# EasyEDA_Source.net
KiCad netlist of a schematic drawn in EasyEDA
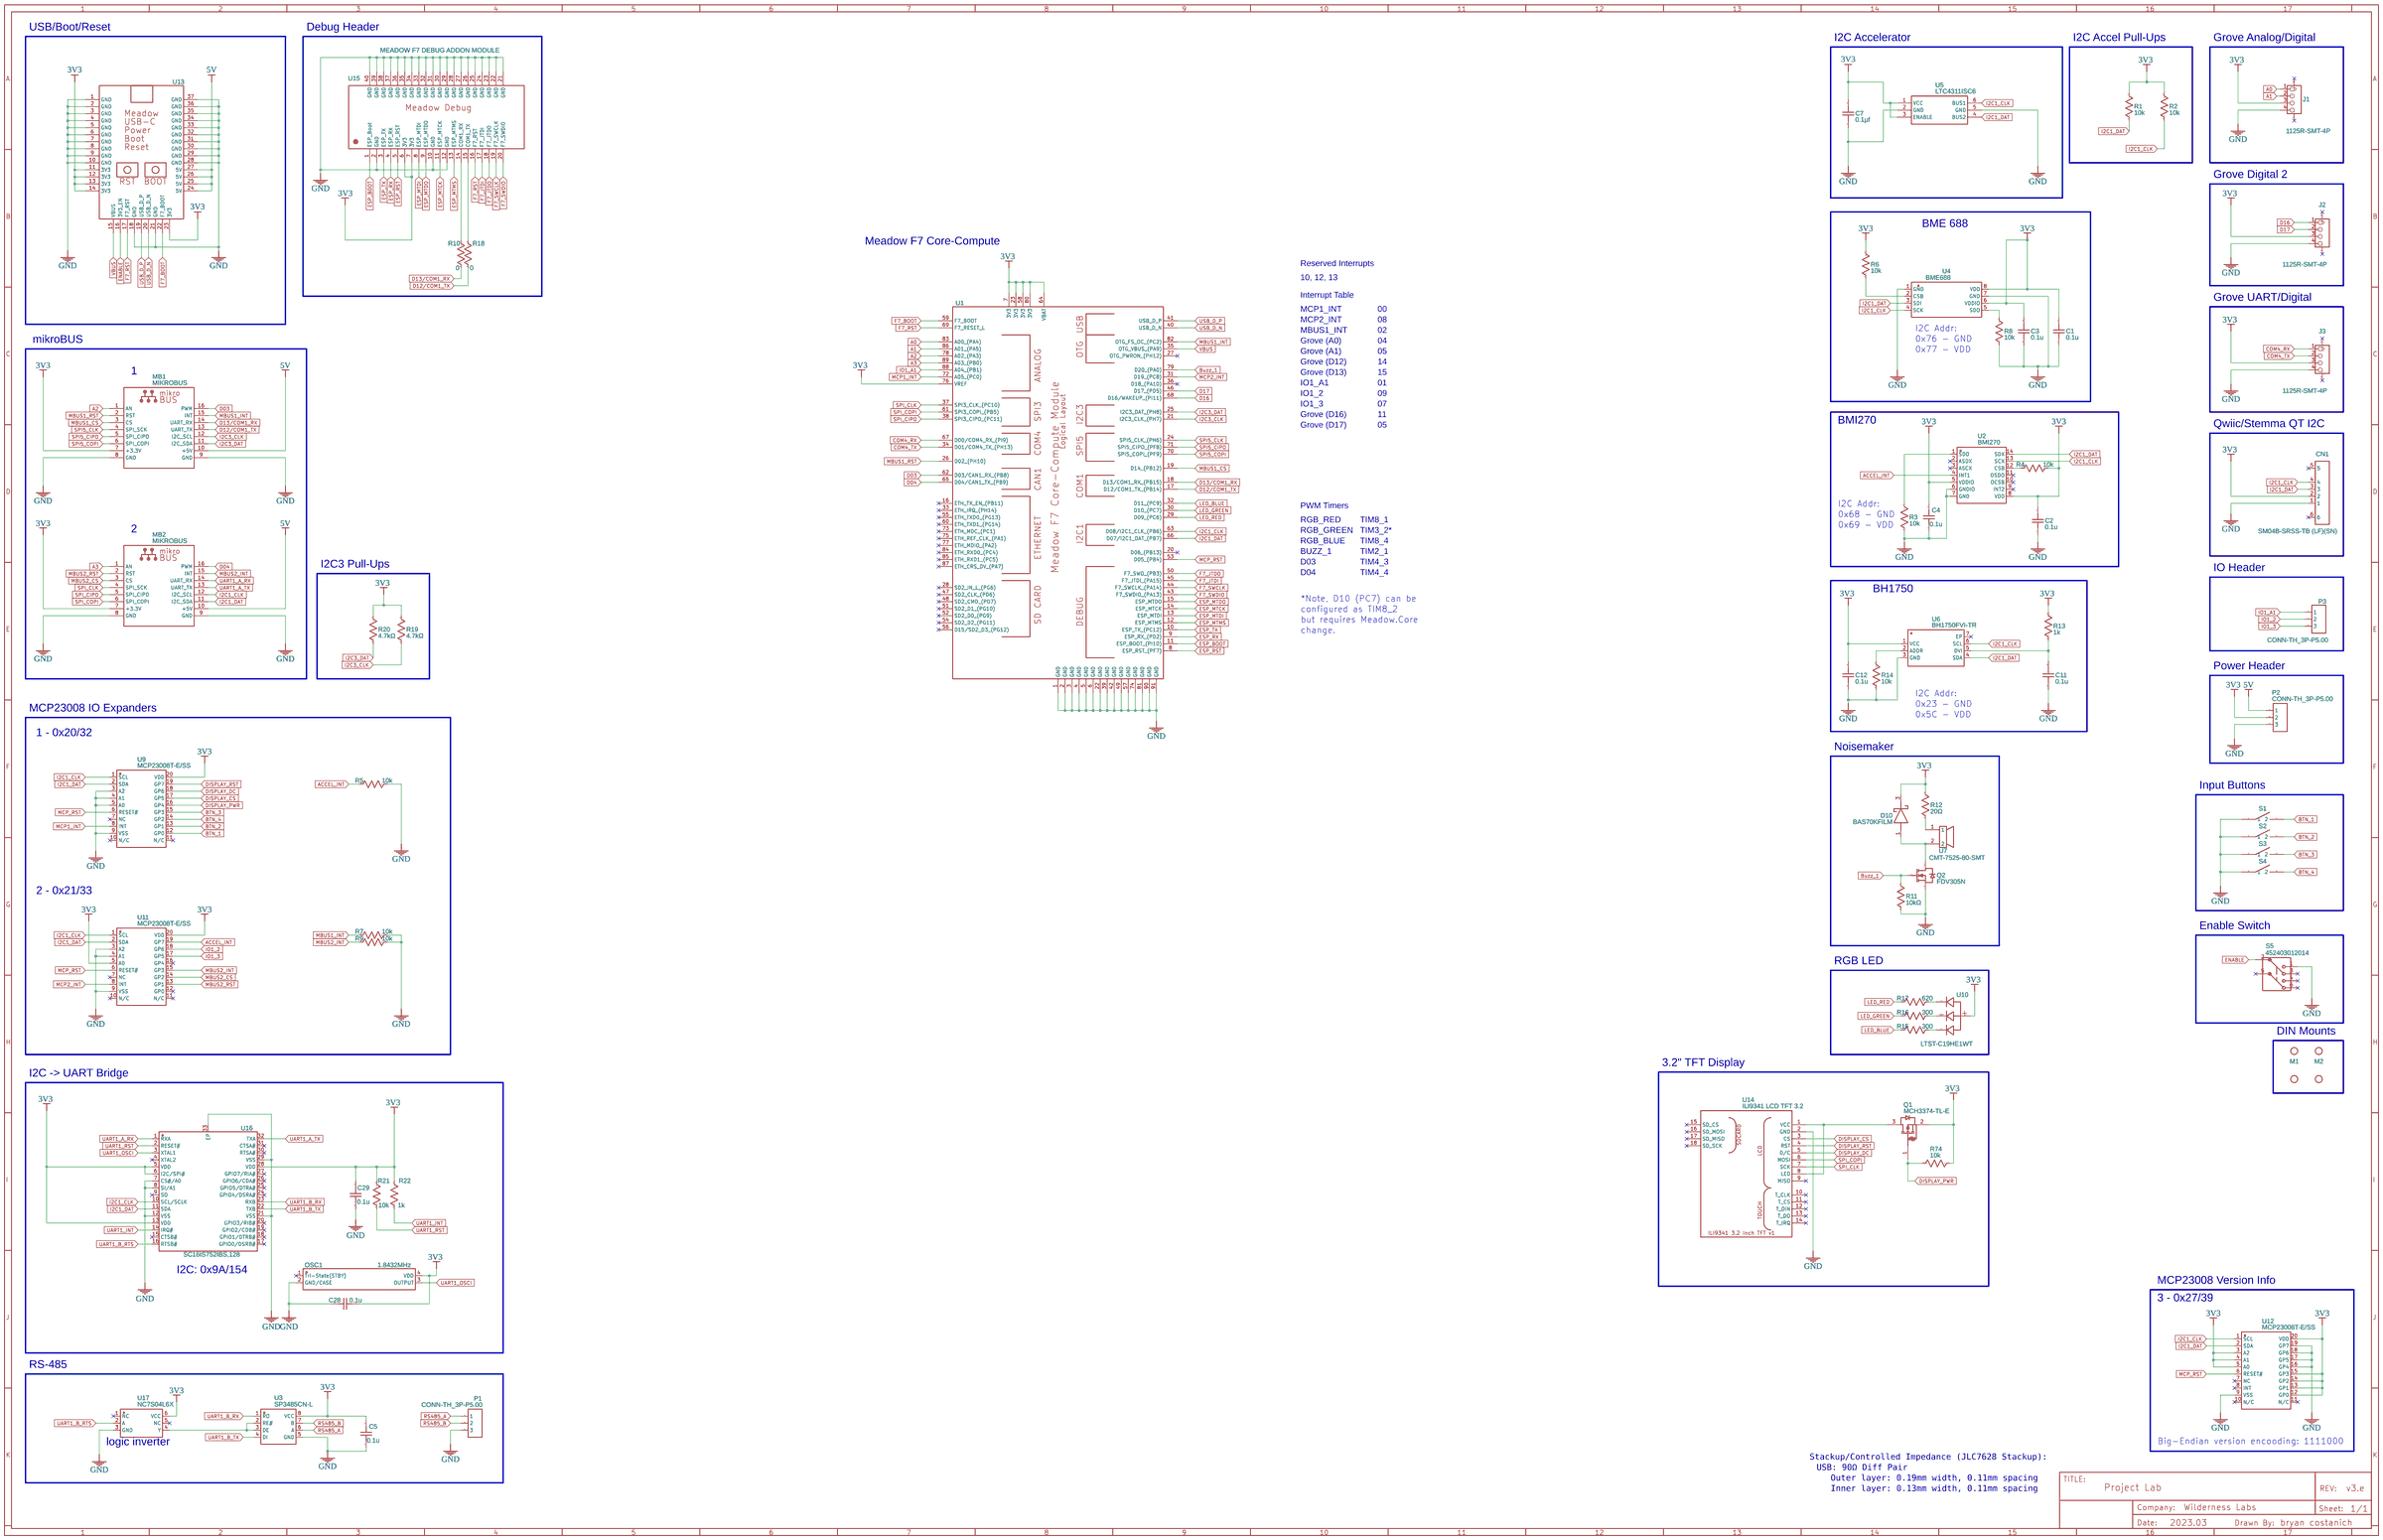
[diagram p0: schematic sheet]

(export (version "E")
  (design (tool "Eeschema 10.0.6"))
  (components
    (comp (ref "C1")
      (value "0.1u")
      (fields (field (name "BOM_Manufacturer Part") "CC0603KRX7R9BB103"))
      (libsource (lib "") (part "C_0402_US"))
    )
    (comp (ref "C2")
      (value "0.1u")
      (fields (field (name "BOM_Manufacturer Part") "CC0603KRX7R9BB103"))
      (libsource (lib "") (part "C_0402_US"))
    )
    (comp (ref "C3")
      (value "0.1u")
      (fields (field (name "BOM_Manufacturer Part") "CC0603KRX7R9BB103"))
      (libsource (lib "") (part "C_0402_US"))
    )
    (comp (ref "C4")
      (value "0.1u")
      (fields (field (name "BOM_Manufacturer Part") "CC0603KRX7R9BB103"))
      (libsource (lib "") (part "C_0402_US"))
    )
    (comp (ref "C5")
      (value "0.1u")
      (fields (field (name "BOM_Manufacturer Part") "CC0603KRX7R9BB103"))
      (libsource (lib "") (part "C_0402_US"))
    )
    (comp (ref "C7")
      (value "0.1µf")
      (fields
        (field (name "BOM_Manufacturer Part") "CC0603KRX7R7BB104")
        (field (name "BOM_Supplier Part") "C108079")
      )
      (libsource (lib "") (part "CC0603KRX7R7BB104"))
    )
    (comp (ref "C11")
      (value "0.1u")
      (fields (field (name "BOM_Manufacturer Part") "CC0603KRX7R9BB103"))
      (libsource (lib "") (part "C_0402_US"))
    )
    (comp (ref "C12")
      (value "0.1u")
      (fields (field (name "BOM_Manufacturer Part") "CC0603KRX7R9BB103"))
      (libsource (lib "") (part "C_0402_US"))
    )
    (comp (ref "C28")
      (value "0.1u")
      (fields (field (name "BOM_Manufacturer Part") "CC0603KRX7R7BB104"))
      (libsource (lib "") (part "C_0603_US_1"))
    )
    (comp (ref "C29")
      (value "0.1u")
      (fields (field (name "BOM_Manufacturer Part") "CC0603KRX7R7BB104"))
      (libsource (lib "") (part "C_0603_US"))
    )
    (comp (ref "CN1")
      (value "SM04B-SRSS-TB (LF)(SN)")
      (fields (field (name "BOM_Supplier Part") "C160404"))
      (libsource (lib "") (part "SM04B-SRSS-TB (LF)(SN)"))
    )
    (comp (ref "D10") (value "BAS70KFILM") (libsource (lib "") (part "BAS70KFILM")))
    (comp (ref "J1") (value "1125R-SMT-4P") (libsource (lib "") (part "1125R-SMT-4P")))
    (comp (ref "J2") (value "1125R-SMT-4P") (libsource (lib "") (part "1125R-SMT-4P")))
    (comp (ref "J3") (value "1125R-SMT-4P") (libsource (lib "") (part "1125R-SMT-4P")))
    (comp (ref "M1") (value "DIN_MOUNT_HOLES") (libsource (lib "") (part "DIN_MOUNT_HOLES")))
    (comp (ref "M2") (value "DIN_MOUNT_HOLES") (libsource (lib "") (part "DIN_MOUNT_HOLES")))
    (comp (ref "MB1") (value "MIKROBUS") (libsource (lib "") (part "MIKROBUS")))
    (comp (ref "MB2") (value "MIKROBUS") (libsource (lib "") (part "MIKROBUS")))
    (comp (ref "OSC1")
      (value "1.8432MHz")
      (fields (field (name "BOM_Manufacturer Part") "ASE-1.8432MHZ-LC-T"))
      (libsource (lib "") (part "ASE-1.8432MHZ-C-T3"))
    )
    (comp (ref "P1")
      (value "CONN-TH_3P-P5.00")
      (fields
        (field (name "BOM_Manufacturer Part") "39890-0303")
        (field (name "BOM_Supplier Part") "WM15826-ND")
      )
      (libsource (lib "") (part "CONN-TH_3P-P5.00"))
    )
    (comp (ref "P2")
      (value "CONN-TH_3P-P5.00")
      (fields
        (field (name "BOM_Manufacturer Part") "39890-0303")
        (field (name "BOM_Supplier Part") "WM15826-ND")
      )
      (libsource (lib "") (part "CONN-TH_3P-P5.00"))
    )
    (comp (ref "P3")
      (value "CONN-TH_3P-P5.00")
      (fields
        (field (name "BOM_Manufacturer Part") "39890-0303")
        (field (name "BOM_Supplier Part") "WM15826-ND")
      )
      (libsource (lib "") (part "CONN-TH_3P-P5.00"))
    )
    (comp (ref "Q1") (value "MCH3374-TL-E") (libsource (lib "") (part "MCH3374-TL-E")))
    (comp (ref "Q2")
      (value "FDV305N")
      (fields (field (name "BOM_Supplier Part") "C65189"))
      (libsource (lib "") (part "2N7002"))
    )
    (comp (ref "R1")
      (value "10k")
      (fields (field (name "BOM_Manufacturer Part") "RC0603FR-0710KL"))
      (libsource (lib "") (part "Res_0603(1/10W)_US"))
    )
    (comp (ref "R2")
      (value "10k")
      (fields (field (name "BOM_Manufacturer Part") "RC0603FR-0710KL"))
      (libsource (lib "") (part "Res_0603(1/10W)_US"))
    )
    (comp (ref "R3")
      (value "10k")
      (fields (field (name "BOM_Manufacturer Part") "RC0603FR-0710KL"))
      (libsource (lib "") (part "R_0402_US"))
    )
    (comp (ref "R4")
      (value "10k")
      (fields (field (name "BOM_Manufacturer Part") "RC0603FR-0710KL"))
      (libsource (lib "") (part "R_0402_US_1"))
    )
    (comp (ref "R5")
      (value "10k")
      (fields (field (name "BOM_Manufacturer Part") "RC0603FR-0710KL"))
      (libsource (lib "") (part "R_0402_US_1"))
    )
    (comp (ref "R6")
      (value "10k")
      (fields (field (name "BOM_Manufacturer Part") "RC0603FR-0710KL"))
      (libsource (lib "") (part "R_0402_US"))
    )
    (comp (ref "R7")
      (value "10k")
      (fields (field (name "BOM_Manufacturer Part") "RC0603FR-0710KL"))
      (libsource (lib "") (part "R_0402_US_1"))
    )
    (comp (ref "R8")
      (value "10k")
      (fields (field (name "BOM_Manufacturer Part") "RC0603FR-0710KL"))
      (libsource (lib "") (part "R_0402_US"))
    )
    (comp (ref "R9")
      (value "10k")
      (fields (field (name "BOM_Manufacturer Part") "RC0603FR-0710KL"))
      (libsource (lib "") (part "R_0402_US_1"))
    )
    (comp (ref "R10")
      (value "0")
      (fields (field (name "BOM_Manufacturer Part") "RC0603JR-070RL"))
      (libsource (lib "") (part "R_0603_US"))
    )
    (comp (ref "R11")
      (value "10kΩ")
      (fields (field (name "BOM_Manufacturer Part") "RC0603FR-0710KL"))
      (libsource (lib "") (part "R_0402_US"))
    )
    (comp (ref "R12")
      (value "20Ω")
      (fields (field (name "BOM_Manufacturer Part") "RC0603FR-0720RL"))
      (libsource (lib "") (part "R_0402_US"))
    )
    (comp (ref "R13")
      (value "1k")
      (fields (field (name "BOM_Manufacturer Part") "RC0603FR-071KL"))
      (libsource (lib "") (part "R_0603_US"))
    )
    (comp (ref "R14")
      (value "10k")
      (fields (field (name "BOM_Manufacturer Part") "RC0603FR-0710KL"))
      (libsource (lib "") (part "R_0402_US"))
    )
    (comp (ref "R15")
      (value "300")
      (fields (field (name "BOM_Manufacturer Part") "RC0603FR-07300RL"))
      (libsource (lib "") (part "R_0603_US_1"))
    )
    (comp (ref "R16")
      (value "300")
      (fields (field (name "BOM_Manufacturer Part") "RC0603FR-07300RL"))
      (libsource (lib "") (part "R_0603_US_1"))
    )
    (comp (ref "R17")
      (value "620")
      (fields (field (name "BOM_Manufacturer Part") "RC0603FR-07620RL"))
      (libsource (lib "") (part "R_0603_US_1"))
    )
    (comp (ref "R18")
      (value "0")
      (fields (field (name "BOM_Manufacturer Part") "RC0603JR-070RL"))
      (libsource (lib "") (part "R_0603_US"))
    )
    (comp (ref "R19")
      (value "4.7kΩ")
      (fields (field (name "BOM_Manufacturer Part") "RC0603FR-074K7L"))
      (libsource (lib "") (part "Res_0603(1/10W)_US"))
    )
    (comp (ref "R20")
      (value "4.7kΩ")
      (fields (field (name "BOM_Manufacturer Part") "RC0603FR-074K7L"))
      (libsource (lib "") (part "Res_0603(1/10W)_US"))
    )
    (comp (ref "R21")
      (value "10k")
      (fields (field (name "BOM_Manufacturer Part") "RC0603FR-0710KL"))
      (libsource (lib "") (part "R_0603_US_2"))
    )
    (comp (ref "R22")
      (value "1k")
      (fields (field (name "BOM_Manufacturer Part") "RC0603FR-071KL"))
      (libsource (lib "") (part "R_0402_US_2"))
    )
    (comp (ref "R74")
      (value "10k")
      (fields (field (name "BOM_Manufacturer Part") "RC0603FR-0710KL"))
      (libsource (lib "") (part "R_0603_US_3"))
    )
    (comp (ref "S1") (value "Up") (libsource (lib "") (part "Tactile Switch 6x6 SMD")))
    (comp (ref "S2") (value "Down") (libsource (lib "") (part "Tactile Switch 6x6 SMD")))
    (comp (ref "S3") (value "Down") (libsource (lib "") (part "Tactile Switch 6x6 SMD")))
    (comp (ref "S4") (value "Down") (libsource (lib "") (part "Tactile Switch 6x6 SMD")))
    (comp (ref "S5") (value "452403012014") (libsource (lib "") (part "452403012014")))
    (comp (ref "U1")
      (value "Meadow F7v2 Core-Compute Module - Logical")
      (libsource (lib "") (part "Meadow F7v2 Core-Compute Module - Logical"))
    )
    (comp (ref "U2")
      (value "BMI270")
      (fields (field (name "BOM_Supplier Part") "C2836813"))
      (libsource (lib "") (part "BMI270"))
    )
    (comp (ref "U3")
      (value "SP3485CN-L")
      (fields (field (name "BOM_Supplier Part") "C916153"))
      (libsource (lib "") (part "SP3485CN-L"))
    )
    (comp (ref "U4") (value "BME688") (libsource (lib "") (part "BME680")))
    (comp (ref "U5")
      (value "LTC4311ISC6")
      (fields (field (name "BOM_Manufacturer Part") "LTC4311ISC6#TRPBF"))
      (libsource (lib "") (part "LTC4311ISC6"))
    )
    (comp (ref "U6")
      (value "BH1750FVI-TR")
      (fields (field (name "BOM_Supplier Part") "C78960"))
      (libsource (lib "") (part "BH1750FVI-TR"))
    )
    (comp (ref "U7") (value "CMT-7525-80-SMT") (libsource (lib "") (part "CMT-7525-80-SMT")))
    (comp (ref "U8")
      (value "WILDERNESS_LABS_LOGO_HORIZONTAL")
      (libsource (lib "") (part "WILDERNESS_LABS_LOGO_HORIZONTAL"))
    )
    (comp (ref "U9")
      (value "MCP23008T-E/SS")
      (fields (field (name "BOM_Supplier Part") "C629435"))
      (libsource (lib "") (part "MCP23008T-E/SS"))
    )
    (comp (ref "U10")
      (value "LTST-C19HE1WT")
      (fields
        (field (name "BOM_Manufacturer Part") "LTST-C19HE1WT-H")
        (field (name "BOM_Supplier Part") "C427425")
      )
      (libsource (lib "") (part "LTST-C19HE1WT-H"))
    )
    (comp (ref "U11")
      (value "MCP23008T-E/SS")
      (fields (field (name "BOM_Supplier Part") "C629435"))
      (libsource (lib "") (part "MCP23008T-E/SS"))
    )
    (comp (ref "U12")
      (value "MCP23008T-E/SS")
      (fields (field (name "BOM_Supplier Part") "C629435"))
      (libsource (lib "") (part "MCP23008T-E/SS"))
    )
    (comp (ref "U13")
      (value "Meadow Core-Compute USB-C, Power, Boot, and Reset Addon Module")
      (libsource (lib "") (part "Meadow Core-Compute USB-C, Power, Boot, and Reset Addon Module"))
    )
    (comp (ref "U14") (value "ILI9341 LCD TFT 3.2") (libsource (lib "") (part "ILI9341 LCD TFT 3.2")))
    (comp (ref "U15")
      (value "MEADOW F7 DEBUG ADDON MODULE")
      (libsource (lib "") (part "MEADOW F7 DEBUG ADDON MODULE"))
    )
    (comp (ref "U16")
      (value "SC16IS752IBS,128")
      (fields (field (name "BOM_Supplier Part") "C2678025"))
      (libsource (lib "") (part "SC16IS752IBS,128"))
    )
    (comp (ref "U17")
      (value "NC7S04L6X")
      (fields (field (name "BOM_Supplier Part") "C895519"))
      (libsource (lib "") (part "NC7S04L6X"))
    )
  )
  (nets
    (net (code "1") (name "3V3") (class "Default")
      (node (ref "C1") (pin "2") (pinfunction "2_2") (pintype "unspecified"))
      (node (ref "C12") (pin "2") (pinfunction "2_2") (pintype "unspecified"))
      (node (ref "C2") (pin "2") (pinfunction "2_2") (pintype "unspecified"))
      (node (ref "C28") (pin "1") (pinfunction "1_1") (pintype "unspecified"))
      (node (ref "C29") (pin "2") (pinfunction "2_2") (pintype "unspecified"))
      (node (ref "C3") (pin "2") (pinfunction "2_2") (pintype "unspecified"))
      (node (ref "C4") (pin "2") (pinfunction "2_2") (pintype "unspecified"))
      (node (ref "C5") (pin "2") (pinfunction "2_2") (pintype "unspecified"))
      (node (ref "C7") (pin "2") (pinfunction "2_2") (pintype "unspecified"))
      (node (ref "CN1") (pin "2") (pinfunction "2_2") (pintype "unspecified"))
      (node (ref "D10") (pin "3") (pinfunction "K_3") (pintype "bidirectional"))
      (node (ref "J1") (pin "3") (pinfunction "3_3") (pintype "unspecified"))
      (node (ref "J2") (pin "3") (pinfunction "3_3") (pintype "unspecified"))
      (node (ref "J3") (pin "3") (pinfunction "3_3") (pintype "unspecified"))
      (node (ref "MB1") (pin "7") (pinfunction "+3.3V_7") (pintype "unspecified"))
      (node (ref "MB2") (pin "7") (pinfunction "+3.3V_7") (pintype "unspecified"))
      (node (ref "OSC1") (pin "4") (pinfunction "VDD_4") (pintype "unspecified"))
      (node (ref "P2") (pin "2") (pinfunction "2_2") (pintype "unspecified"))
      (node (ref "Q1") (pin "2") (pinfunction "S_2") (pintype "unspecified"))
      (node (ref "R1") (pin "2") (pinfunction "2_2") (pintype "unspecified"))
      (node (ref "R12") (pin "2") (pinfunction "2_2") (pintype "unspecified"))
      (node (ref "R13") (pin "2") (pinfunction "2_2") (pintype "unspecified"))
      (node (ref "R19") (pin "2") (pinfunction "2_2") (pintype "unspecified"))
      (node (ref "R2") (pin "2") (pinfunction "2_2") (pintype "unspecified"))
      (node (ref "R20") (pin "2") (pinfunction "2_2") (pintype "unspecified"))
      (node (ref "R21") (pin "1") (pinfunction "1_1") (pintype "unspecified"))
      (node (ref "R22") (pin "1") (pinfunction "1_1") (pintype "unspecified"))
      (node (ref "R4") (pin "1") (pinfunction "1_1") (pintype "unspecified"))
      (node (ref "R6") (pin "2") (pinfunction "2_2") (pintype "unspecified"))
      (node (ref "R74") (pin "1") (pinfunction "1_1") (pintype "unspecified"))
      (node (ref "U1") (pin "23") (pinfunction "3V3_23") (pintype "unspecified"))
      (node (ref "U1") (pin "58") (pinfunction "3V3_58") (pintype "passive"))
      (node (ref "U1") (pin "64") (pinfunction "VBAT_64") (pintype "input"))
      (node (ref "U1") (pin "7") (pinfunction "3V3_7") (pintype "unspecified"))
      (node (ref "U1") (pin "76") (pinfunction "VREF_76") (pintype "input"))
      (node (ref "U1") (pin "80") (pinfunction "3V3_80") (pintype "unspecified"))
      (node (ref "U10") (pin "4") (pinfunction "A_4") (pintype "unspecified"))
      (node (ref "U11") (pin "20") (pinfunction "VDD_20") (pintype "unspecified"))
      (node (ref "U11") (pin "5") (pinfunction "A0_5") (pintype "unspecified"))
      (node (ref "U12") (pin "12") (pinfunction "GP0_12") (pintype "unspecified"))
      (node (ref "U12") (pin "13") (pinfunction "GP1_13") (pintype "unspecified"))
      (node (ref "U12") (pin "14") (pinfunction "GP2_14") (pintype "unspecified"))
      (node (ref "U12") (pin "15") (pinfunction "GP3_15") (pintype "unspecified"))
      (node (ref "U12") (pin "20") (pinfunction "VDD_20") (pintype "unspecified"))
      (node (ref "U12") (pin "3") (pinfunction "A2_3") (pintype "unspecified"))
      (node (ref "U12") (pin "4") (pinfunction "A1_4") (pintype "unspecified"))
      (node (ref "U12") (pin "5") (pinfunction "A0_5") (pintype "unspecified"))
      (node (ref "U13") (pin "11") (pinfunction "3V3_11") (pintype "unspecified"))
      (node (ref "U13") (pin "12") (pinfunction "3V3_12") (pintype "unspecified"))
      (node (ref "U13") (pin "13") (pinfunction "3V3_13") (pintype "unspecified"))
      (node (ref "U13") (pin "14") (pinfunction "3V3_14") (pintype "unspecified"))
      (node (ref "U13") (pin "23") (pinfunction "3V3_23") (pintype "passive"))
      (node (ref "U15") (pin "6") (pinfunction "3V3_6") (pintype "unspecified"))
      (node (ref "U15") (pin "7") (pinfunction "3V3_7") (pintype "unspecified"))
      (node (ref "U16") (pin "13") (pinfunction "VDD_13") (pintype "unspecified"))
      (node (ref "U16") (pin "28") (pinfunction "VDD_28") (pintype "unspecified"))
      (node (ref "U16") (pin "5") (pinfunction "VDD_5") (pintype "unspecified"))
      (node (ref "U16") (pin "6") (pinfunction "I2C/SPI#_6") (pintype "unspecified"))
      (node (ref "U17") (pin "6") (pinfunction "VCC_6") (pintype "unspecified"))
      (node (ref "U2") (pin "5") (pinfunction "VDDIO_5") (pintype "unspecified"))
      (node (ref "U2") (pin "8") (pinfunction "VDD_8") (pintype "unspecified"))
      (node (ref "U3") (pin "8") (pinfunction "VCC_8") (pintype "unspecified"))
      (node (ref "U4") (pin "6") (pinfunction "VDDIO_6") (pintype "unspecified"))
      (node (ref "U4") (pin "8") (pinfunction "VDD_8") (pintype "unspecified"))
      (node (ref "U5") (pin "1") (pinfunction "VCC_1") (pintype "unspecified"))
      (node (ref "U5") (pin "3") (pinfunction "ENABLE_3") (pintype "unspecified"))
      (node (ref "U6") (pin "1") (pinfunction "VCC_1") (pintype "unspecified"))
      (node (ref "U9") (pin "20") (pinfunction "VDD_20") (pintype "unspecified"))
    )
    (net (code "2") (name "5V") (class "Default")
      (node (ref "MB1") (pin "10") (pinfunction "+5V_10") (pintype "unspecified"))
      (node (ref "MB2") (pin "10") (pinfunction "+5V_10") (pintype "unspecified"))
      (node (ref "P2") (pin "1") (pinfunction "1_1") (pintype "unspecified"))
      (node (ref "U13") (pin "24") (pinfunction "5V_24") (pintype "passive"))
      (node (ref "U13") (pin "25") (pinfunction "5V_25") (pintype "passive"))
      (node (ref "U13") (pin "26") (pinfunction "5V_26") (pintype "passive"))
      (node (ref "U13") (pin "27") (pinfunction "5V_27") (pintype "passive"))
    )
    (net (code "3") (name "A0") (class "Default")
      (node (ref "J1") (pin "1") (pinfunction "1_1") (pintype "unspecified"))
      (node (ref "U1") (pin "83") (pinfunction "A00_(PA4)_83") (pintype "unspecified"))
    )
    (net (code "4") (name "A1") (class "Default")
      (node (ref "J1") (pin "2") (pinfunction "2_2") (pintype "unspecified"))
      (node (ref "U1") (pin "86") (pinfunction "A01_(PA5)_86") (pintype "unspecified"))
    )
    (net (code "5") (name "A2") (class "Default")
      (node (ref "MB1") (pin "1") (pinfunction "AN_1") (pintype "unspecified"))
      (node (ref "U1") (pin "78") (pinfunction "A02_(PA3)_78") (pintype "unspecified"))
    )
    (net (code "6") (name "A3") (class "Default")
      (node (ref "MB2") (pin "1") (pinfunction "AN_1") (pintype "unspecified"))
      (node (ref "U1") (pin "89") (pinfunction "A03_(PB0)_89") (pintype "unspecified"))
    )
    (net (code "7") (name "ACCEL_INT") (class "Default")
      (node (ref "R5") (pin "2") (pinfunction "2_2") (pintype "unspecified"))
      (node (ref "U11") (pin "19") (pinfunction "GP7_19") (pintype "unspecified"))
      (node (ref "U2") (pin "4") (pinfunction "INT1_4") (pintype "unspecified"))
    )
    (net (code "8") (name "BTN_1") (class "Default")
      (node (ref "S1") (pin "B1") (pinfunction "2_B1") (pintype "unspecified"))
      (node (ref "U9") (pin "12") (pinfunction "GP0_12") (pintype "unspecified"))
    )
    (net (code "9") (name "BTN_2") (class "Default")
      (node (ref "S2") (pin "B1") (pinfunction "2_B1") (pintype "unspecified"))
      (node (ref "U9") (pin "13") (pinfunction "GP1_13") (pintype "unspecified"))
    )
    (net (code "10") (name "BTN_3") (class "Default")
      (node (ref "S3") (pin "B1") (pinfunction "2_B1") (pintype "unspecified"))
      (node (ref "U9") (pin "15") (pinfunction "GP3_15") (pintype "unspecified"))
    )
    (net (code "11") (name "BTN_4") (class "Default")
      (node (ref "S4") (pin "B1") (pinfunction "2_B1") (pintype "unspecified"))
      (node (ref "U9") (pin "14") (pinfunction "GP2_14") (pintype "unspecified"))
    )
    (net (code "12") (name "Buzz_1") (class "Default")
      (node (ref "Q2") (pin "1") (pinfunction "G_1") (pintype "unspecified"))
      (node (ref "R11") (pin "2") (pinfunction "2_2") (pintype "unspecified"))
      (node (ref "U1") (pin "79") (pinfunction "D20_(PA0)_79") (pintype "unspecified"))
    )
    (net (code "13") (name "COM4_RX") (class "Default")
      (node (ref "J3") (pin "1") (pinfunction "1_1") (pintype "unspecified"))
      (node (ref "U1") (pin "67") (pinfunction "D00/COM4_RX_(PI9)_67") (pintype "unspecified"))
    )
    (net (code "14") (name "COM4_TX") (class "Default")
      (node (ref "J3") (pin "2") (pinfunction "2_2") (pintype "unspecified"))
      (node (ref "U1") (pin "34") (pinfunction "D01/COM4_TX_(PH13)_34") (pintype "unspecified"))
    )
    (net (code "15") (name "D03") (class "Default")
      (node (ref "MB1") (pin "16") (pinfunction "PWM_16") (pintype "unspecified"))
      (node (ref "U1") (pin "62") (pinfunction "D03/CAN1_RX_(PB8)_62") (pintype "unspecified"))
    )
    (net (code "16") (name "D04") (class "Default")
      (node (ref "MB2") (pin "16") (pinfunction "PWM_16") (pintype "unspecified"))
      (node (ref "U1") (pin "65") (pinfunction "D04/CAN1_TX_(PB9)_65") (pintype "unspecified"))
    )
    (net (code "17") (name "D12{slash}COM1_TX") (class "Default")
      (node (ref "MB1") (pin "13") (pinfunction "UART_TX_13") (pintype "unspecified"))
      (node (ref "R18") (pin "1") (pinfunction "1_1") (pintype "unspecified"))
      (node (ref "U1") (pin "17") (pinfunction "D12/COM1_TX_(PB14)_17") (pintype "unspecified"))
    )
    (net (code "18") (name "D13{slash}COM1_RX") (class "Default")
      (node (ref "MB1") (pin "14") (pinfunction "UART_RX_14") (pintype "unspecified"))
      (node (ref "R10") (pin "1") (pinfunction "1_1") (pintype "unspecified"))
      (node (ref "U1") (pin "18") (pinfunction "D13/COM1_RX_(PB15)_18") (pintype "unspecified"))
    )
    (net (code "19") (name "D16") (class "Default")
      (node (ref "J2") (pin "1") (pinfunction "1_1") (pintype "unspecified"))
      (node (ref "U1") (pin "68") (pinfunction "D16/WAKEUP_(PI11)_68") (pintype "unspecified"))
    )
    (net (code "20") (name "D17") (class "Default")
      (node (ref "J2") (pin "2") (pinfunction "2_2") (pintype "unspecified"))
      (node (ref "U1") (pin "46") (pinfunction "D17_(PD5)_46") (pintype "unspecified"))
    )
    (net (code "21") (name "DISPLAY_CS") (class "Default")
      (node (ref "U14") (pin "3") (pinfunction "CS_3") (pintype "unspecified"))
      (node (ref "U9") (pin "17") (pinfunction "GP5_17") (pintype "unspecified"))
    )
    (net (code "22") (name "DISPLAY_DC") (class "Default")
      (node (ref "U14") (pin "5") (pinfunction "D/C_5") (pintype "unspecified"))
      (node (ref "U9") (pin "18") (pinfunction "GP6_18") (pintype "unspecified"))
    )
    (net (code "23") (name "DISPLAY_PWR") (class "Default")
      (node (ref "Q1") (pin "1") (pinfunction "G_1") (pintype "unspecified"))
      (node (ref "R74") (pin "2") (pinfunction "2_2") (pintype "unspecified"))
      (node (ref "U9") (pin "16") (pinfunction "GP4_16") (pintype "unspecified"))
    )
    (net (code "24") (name "DISPLAY_RST") (class "Default")
      (node (ref "U14") (pin "4") (pinfunction "RST_4") (pintype "unspecified"))
      (node (ref "U9") (pin "19") (pinfunction "GP7_19") (pintype "unspecified"))
    )
    (net (code "25") (name "ENABLE") (class "Default")
      (node (ref "S5") (pin "2") (pinfunction "1_2") (pintype "unspecified"))
      (node (ref "U13") (pin "16") (pinfunction "3V3_EN_16") (pintype "unspecified"))
    )
    (net (code "26") (name "ESP_BOOT") (class "Default")
      (node (ref "U1") (pin "11") (pinfunction "ESP_BOOT_(PI10)_11") (pintype "unspecified"))
      (node (ref "U15") (pin "1") (pinfunction "ESP_Boot_1") (pintype "unspecified"))
    )
    (net (code "27") (name "ESP_MTCK") (class "Default")
      (node (ref "U1") (pin "14") (pinfunction "ESP_MTCK_14") (pintype "unspecified"))
      (node (ref "U15") (pin "11") (pinfunction "ESP_MTCK_11") (pintype "unspecified"))
    )
    (net (code "28") (name "ESP_MTDI") (class "Default")
      (node (ref "U1") (pin "13") (pinfunction "ESP_MTDI_13") (pintype "unspecified"))
      (node (ref "U15") (pin "8") (pinfunction "ESP_MTDI_8") (pintype "unspecified"))
    )
    (net (code "29") (name "ESP_MTDO") (class "Default")
      (node (ref "U1") (pin "15") (pinfunction "ESP_MTDO_15") (pintype "unspecified"))
      (node (ref "U15") (pin "9") (pinfunction "ESP_MTDO_9") (pintype "unspecified"))
    )
    (net (code "30") (name "ESP_MTMS") (class "Default")
      (node (ref "U1") (pin "12") (pinfunction "ESP_MTMS_12") (pintype "unspecified"))
      (node (ref "U15") (pin "13") (pinfunction "ESP_MTMS_13") (pintype "unspecified"))
    )
    (net (code "31") (name "ESP_RST") (class "Default")
      (node (ref "U1") (pin "8") (pinfunction "ESP_RST_(PF7)_8") (pintype "unspecified"))
      (node (ref "U15") (pin "5") (pinfunction "ESP_RST_5") (pintype "unspecified"))
    )
    (net (code "32") (name "ESP_RX") (class "Default")
      (node (ref "U1") (pin "9") (pinfunction "ESP_RX_(PD2)_9") (pintype "unspecified"))
      (node (ref "U15") (pin "4") (pinfunction "ESP_RX_4") (pintype "unspecified"))
    )
    (net (code "33") (name "ESP_TX") (class "Default")
      (node (ref "U1") (pin "10") (pinfunction "ESP_TX_(PC12)_10") (pintype "unspecified"))
      (node (ref "U15") (pin "3") (pinfunction "ESP_TX_3") (pintype "unspecified"))
    )
    (net (code "34") (name "F7_BOOT") (class "Default")
      (node (ref "U1") (pin "59") (pinfunction "F7_BOOT_59") (pintype "unspecified"))
      (node (ref "U13") (pin "22") (pinfunction "F7_BOOT_22") (pintype "unspecified"))
    )
    (net (code "35") (name "F7_JTDI") (class "Default")
      (node (ref "U1") (pin "45") (pinfunction "F7_JTDI_(PA15)_45") (pintype "unspecified"))
      (node (ref "U15") (pin "17") (pinfunction "F7_JTDI_17") (pintype "unspecified"))
    )
    (net (code "36") (name "F7_JTDO") (class "Default")
      (node (ref "U1") (pin "50") (pinfunction "F7_SWO_(PB3)_50") (pintype "unspecified"))
      (node (ref "U15") (pin "18") (pinfunction "F7_JTDO_18") (pintype "unspecified"))
    )
    (net (code "37") (name "F7_RST") (class "Default")
      (node (ref "U1") (pin "69") (pinfunction "F7_RESET_L_69") (pintype "unspecified"))
      (node (ref "U13") (pin "17") (pinfunction "F7_RST_17") (pintype "unspecified"))
      (node (ref "U15") (pin "16") (pinfunction "F7_RST_16") (pintype "unspecified"))
    )
    (net (code "38") (name "F7_SWCLK") (class "Default")
      (node (ref "U1") (pin "44") (pinfunction "F7_SWCLK_(PA14)_44") (pintype "unspecified"))
      (node (ref "U15") (pin "19") (pinfunction "F7_SWCLK_19") (pintype "unspecified"))
    )
    (net (code "39") (name "F7_SWDIO") (class "Default")
      (node (ref "U1") (pin "43") (pinfunction "F7_SWDIO_(PA13)_43") (pintype "unspecified"))
      (node (ref "U15") (pin "20") (pinfunction "F7_SWDIO_20") (pintype "unspecified"))
    )
    (net (code "40") (name "GND") (class "Default")
      (node (ref "C1") (pin "1") (pinfunction "1_1") (pintype "unspecified"))
      (node (ref "C11") (pin "1") (pinfunction "1_1") (pintype "unspecified"))
      (node (ref "C12") (pin "1") (pinfunction "1_1") (pintype "unspecified"))
      (node (ref "C2") (pin "1") (pinfunction "1_1") (pintype "unspecified"))
      (node (ref "C28") (pin "2") (pinfunction "2_2") (pintype "unspecified"))
      (node (ref "C29") (pin "1") (pinfunction "1_1") (pintype "unspecified"))
      (node (ref "C3") (pin "1") (pinfunction "1_1") (pintype "unspecified"))
      (node (ref "C4") (pin "1") (pinfunction "1_1") (pintype "unspecified"))
      (node (ref "C5") (pin "1") (pinfunction "1_1") (pintype "unspecified"))
      (node (ref "C7") (pin "1") (pinfunction "1_1") (pintype "unspecified"))
      (node (ref "CN1") (pin "1") (pinfunction "1_1") (pintype "unspecified"))
      (node (ref "J1") (pin "4") (pinfunction "4_4") (pintype "unspecified"))
      (node (ref "J2") (pin "4") (pinfunction "4_4") (pintype "unspecified"))
      (node (ref "J3") (pin "4") (pinfunction "4_4") (pintype "unspecified"))
      (node (ref "MB1") (pin "8") (pinfunction "GND_8") (pintype "unspecified"))
      (node (ref "MB1") (pin "9") (pinfunction "GND_9") (pintype "unspecified"))
      (node (ref "MB2") (pin "8") (pinfunction "GND_8") (pintype "unspecified"))
      (node (ref "MB2") (pin "9") (pinfunction "GND_9") (pintype "unspecified"))
      (node (ref "OSC1") (pin "2") (pinfunction "GND/CASE_2") (pintype "unspecified"))
      (node (ref "P1") (pin "3") (pinfunction "3_3") (pintype "unspecified"))
      (node (ref "P2") (pin "3") (pinfunction "3_3") (pintype "unspecified"))
      (node (ref "Q2") (pin "2") (pinfunction "S_2") (pintype "unspecified"))
      (node (ref "R11") (pin "1") (pinfunction "1_1") (pintype "unspecified"))
      (node (ref "R14") (pin "1") (pinfunction "1_1") (pintype "unspecified"))
      (node (ref "R3") (pin "1") (pinfunction "1_1") (pintype "unspecified"))
      (node (ref "R5") (pin "1") (pinfunction "1_1") (pintype "unspecified"))
      (node (ref "R7") (pin "1") (pinfunction "1_1") (pintype "unspecified"))
      (node (ref "R8") (pin "1") (pinfunction "1_1") (pintype "unspecified"))
      (node (ref "R9") (pin "1") (pinfunction "1_1") (pintype "unspecified"))
      (node (ref "S1") (pin "A1") (pinfunction "1_A1") (pintype "unspecified"))
      (node (ref "S2") (pin "A1") (pinfunction "1_A1") (pintype "unspecified"))
      (node (ref "S3") (pin "A1") (pinfunction "1_A1") (pintype "unspecified"))
      (node (ref "S4") (pin "A1") (pinfunction "1_A1") (pintype "unspecified"))
      (node (ref "S5") (pin "1") (pinfunction "1_1") (pintype "unspecified"))
      (node (ref "U1") (pin "1") (pinfunction "GND_1") (pintype "passive"))
      (node (ref "U1") (pin "2") (pinfunction "GND_2") (pintype "passive"))
      (node (ref "U1") (pin "22") (pinfunction "GND_22") (pintype "passive"))
      (node (ref "U1") (pin "3") (pinfunction "GND_3") (pintype "passive"))
      (node (ref "U1") (pin "39") (pinfunction "GND_39") (pintype "passive"))
      (node (ref "U1") (pin "4") (pinfunction "GND_4") (pintype "passive"))
      (node (ref "U1") (pin "42") (pinfunction "GND_42") (pintype "passive"))
      (node (ref "U1") (pin "49") (pinfunction "GND_49") (pintype "passive"))
      (node (ref "U1") (pin "5") (pinfunction "GND_5") (pintype "passive"))
      (node (ref "U1") (pin "57") (pinfunction "GND_57") (pintype "passive"))
      (node (ref "U1") (pin "6") (pinfunction "GND_6") (pintype "passive"))
      (node (ref "U1") (pin "74") (pinfunction "GND_74") (pintype "passive"))
      (node (ref "U1") (pin "81") (pinfunction "GND_81") (pintype "passive"))
      (node (ref "U1") (pin "90") (pinfunction "GND_90") (pintype "passive"))
      (node (ref "U1") (pin "91") (pinfunction "GND_91") (pintype "passive"))
      (node (ref "U11") (pin "3") (pinfunction "A2_3") (pintype "unspecified"))
      (node (ref "U11") (pin "4") (pinfunction "A1_4") (pintype "unspecified"))
      (node (ref "U11") (pin "9") (pinfunction "VSS_9") (pintype "unspecified"))
      (node (ref "U12") (pin "16") (pinfunction "GP4_16") (pintype "unspecified"))
      (node (ref "U12") (pin "17") (pinfunction "GP5_17") (pintype "unspecified"))
      (node (ref "U12") (pin "18") (pinfunction "GP6_18") (pintype "unspecified"))
      (node (ref "U12") (pin "19") (pinfunction "GP7_19") (pintype "unspecified"))
      (node (ref "U12") (pin "9") (pinfunction "VSS_9") (pintype "unspecified"))
      (node (ref "U13") (pin "1") (pinfunction "GND_1") (pintype "unspecified"))
      (node (ref "U13") (pin "10") (pinfunction "GND_10") (pintype "unspecified"))
      (node (ref "U13") (pin "18") (pinfunction "GND_18") (pintype "unspecified"))
      (node (ref "U13") (pin "2") (pinfunction "GND_2") (pintype "unspecified"))
      (node (ref "U13") (pin "21") (pinfunction "GND_21") (pintype "unspecified"))
      (node (ref "U13") (pin "28") (pinfunction "GND_28") (pintype "unspecified"))
      (node (ref "U13") (pin "29") (pinfunction "GND_29") (pintype "unspecified"))
      (node (ref "U13") (pin "3") (pinfunction "GND_3") (pintype "unspecified"))
      (node (ref "U13") (pin "30") (pinfunction "GND_30") (pintype "unspecified"))
      (node (ref "U13") (pin "31") (pinfunction "GND_31") (pintype "unspecified"))
      (node (ref "U13") (pin "32") (pinfunction "GND_32") (pintype "unspecified"))
      (node (ref "U13") (pin "33") (pinfunction "GND_33") (pintype "unspecified"))
      (node (ref "U13") (pin "34") (pinfunction "GND_34") (pintype "unspecified"))
      (node (ref "U13") (pin "35") (pinfunction "GND_35") (pintype "unspecified"))
      (node (ref "U13") (pin "36") (pinfunction "GND_36") (pintype "unspecified"))
      (node (ref "U13") (pin "37") (pinfunction "GND_37") (pintype "unspecified"))
      (node (ref "U13") (pin "4") (pinfunction "GND_4") (pintype "unspecified"))
      (node (ref "U13") (pin "5") (pinfunction "GND_5") (pintype "unspecified"))
      (node (ref "U13") (pin "6") (pinfunction "GND_6") (pintype "unspecified"))
      (node (ref "U13") (pin "7") (pinfunction "GND_7") (pintype "unspecified"))
      (node (ref "U13") (pin "8") (pinfunction "GND_8") (pintype "unspecified"))
      (node (ref "U13") (pin "9") (pinfunction "GND_9") (pintype "unspecified"))
      (node (ref "U14") (pin "2") (pinfunction "GND_2") (pintype "unspecified"))
      (node (ref "U15") (pin "10") (pinfunction "GND_10") (pintype "unspecified"))
      (node (ref "U15") (pin "12") (pinfunction "GND_12") (pintype "unspecified"))
      (node (ref "U15") (pin "2") (pinfunction "GND_2") (pintype "unspecified"))
      (node (ref "U15") (pin "21") (pinfunction "GND_21") (pintype "unspecified"))
      (node (ref "U15") (pin "22") (pinfunction "GND_22") (pintype "unspecified"))
      (node (ref "U15") (pin "23") (pinfunction "GND_23") (pintype "unspecified"))
      (node (ref "U15") (pin "24") (pinfunction "GND_24") (pintype "unspecified"))
      (node (ref "U15") (pin "25") (pinfunction "GND_25") (pintype "unspecified"))
      (node (ref "U15") (pin "26") (pinfunction "GND_26") (pintype "unspecified"))
      (node (ref "U15") (pin "27") (pinfunction "GND_27") (pintype "unspecified"))
      (node (ref "U15") (pin "28") (pinfunction "GND_28") (pintype "unspecified"))
      (node (ref "U15") (pin "29") (pinfunction "GND_29") (pintype "unspecified"))
      (node (ref "U15") (pin "30") (pinfunction "GND_30") (pintype "unspecified"))
      (node (ref "U15") (pin "31") (pinfunction "GND_31") (pintype "unspecified"))
      (node (ref "U15") (pin "32") (pinfunction "GND_32") (pintype "unspecified"))
      (node (ref "U15") (pin "33") (pinfunction "GND_33") (pintype "unspecified"))
      (node (ref "U15") (pin "34") (pinfunction "GND_34") (pintype "unspecified"))
      (node (ref "U15") (pin "35") (pinfunction "GND_35") (pintype "unspecified"))
      (node (ref "U15") (pin "36") (pinfunction "GND_36") (pintype "unspecified"))
      (node (ref "U15") (pin "37") (pinfunction "GND_37") (pintype "unspecified"))
      (node (ref "U15") (pin "38") (pinfunction "GND_38") (pintype "unspecified"))
      (node (ref "U15") (pin "39") (pinfunction "GND_39") (pintype "unspecified"))
      (node (ref "U15") (pin "40") (pinfunction "GND_40") (pintype "unspecified"))
      (node (ref "U16") (pin "12") (pinfunction "VSS_12") (pintype "unspecified"))
      (node (ref "U16") (pin "21") (pinfunction "VSS_21") (pintype "unspecified"))
      (node (ref "U16") (pin "29") (pinfunction "VSS_29") (pintype "unspecified"))
      (node (ref "U16") (pin "33") (pinfunction "EP_33") (pintype "unspecified"))
      (node (ref "U16") (pin "7") (pinfunction "CS#/A0_7") (pintype "unspecified"))
      (node (ref "U16") (pin "8") (pinfunction "SI/A1_8") (pintype "unspecified"))
      (node (ref "U17") (pin "3") (pinfunction "GND_3") (pintype "unspecified"))
      (node (ref "U2") (pin "6") (pinfunction "GNDIO_6") (pintype "unspecified"))
      (node (ref "U2") (pin "7") (pinfunction "GND_7") (pintype "unspecified"))
      (node (ref "U3") (pin "5") (pinfunction "GND_5") (pintype "unspecified"))
      (node (ref "U4") (pin "1") (pinfunction "GND_1") (pintype "unspecified"))
      (node (ref "U4") (pin "7") (pinfunction "GND_7") (pintype "unspecified"))
      (node (ref "U5") (pin "2") (pinfunction "GND_2") (pintype "unspecified"))
      (node (ref "U5") (pin "5") (pinfunction "GND_5") (pintype "unspecified"))
      (node (ref "U6") (pin "3") (pinfunction "GND_3") (pintype "unspecified"))
      (node (ref "U9") (pin "3") (pinfunction "A2_3") (pintype "unspecified"))
      (node (ref "U9") (pin "4") (pinfunction "A1_4") (pintype "unspecified"))
      (node (ref "U9") (pin "5") (pinfunction "A0_5") (pintype "unspecified"))
      (node (ref "U9") (pin "9") (pinfunction "VSS_9") (pintype "unspecified"))
    )
    (net (code "41") (name "I2C1_CLK") (class "Default")
      (node (ref "CN1") (pin "4") (pinfunction "4_4") (pintype "unspecified"))
      (node (ref "MB2") (pin "12") (pinfunction "I2C_SCL_12") (pintype "unspecified"))
      (node (ref "R2") (pin "1") (pinfunction "1_1") (pintype "unspecified"))
      (node (ref "U1") (pin "63") (pinfunction "D08/I2C1_CLK_(PB6)_63") (pintype "unspecified"))
      (node (ref "U11") (pin "1") (pinfunction "SCL_1") (pintype "unspecified"))
      (node (ref "U12") (pin "1") (pinfunction "SCL_1") (pintype "unspecified"))
      (node (ref "U16") (pin "10") (pinfunction "SCL/SCLK_10") (pintype "unspecified"))
      (node (ref "U2") (pin "13") (pinfunction "SCX_13") (pintype "unspecified"))
      (node (ref "U4") (pin "4") (pinfunction "SCK_4") (pintype "unspecified"))
      (node (ref "U5") (pin "6") (pinfunction "BUS1_6") (pintype "unspecified"))
      (node (ref "U6") (pin "6") (pinfunction "SCL_6") (pintype "unspecified"))
      (node (ref "U9") (pin "1") (pinfunction "SCL_1") (pintype "unspecified"))
    )
    (net (code "42") (name "I2C1_DAT") (class "Default")
      (node (ref "CN1") (pin "3") (pinfunction "3_3") (pintype "unspecified"))
      (node (ref "MB2") (pin "11") (pinfunction "I2C_SDA_11") (pintype "unspecified"))
      (node (ref "R1") (pin "1") (pinfunction "1_1") (pintype "unspecified"))
      (node (ref "U1") (pin "66") (pinfunction "D07/I2C1_DAT_(PB7)_66") (pintype "unspecified"))
      (node (ref "U11") (pin "2") (pinfunction "SDA_2") (pintype "unspecified"))
      (node (ref "U12") (pin "2") (pinfunction "SDA_2") (pintype "unspecified"))
      (node (ref "U16") (pin "11") (pinfunction "SDA_11") (pintype "unspecified"))
      (node (ref "U2") (pin "14") (pinfunction "SDX_14") (pintype "unspecified"))
      (node (ref "U4") (pin "3") (pinfunction "SDI_3") (pintype "unspecified"))
      (node (ref "U5") (pin "4") (pinfunction "BUS2_4") (pintype "unspecified"))
      (node (ref "U6") (pin "4") (pinfunction "SDA_4") (pintype "unspecified"))
      (node (ref "U9") (pin "2") (pinfunction "SDA_2") (pintype "unspecified"))
    )
    (net (code "43") (name "I2C3_CLK") (class "Default")
      (node (ref "MB1") (pin "12") (pinfunction "I2C_SCL_12") (pintype "unspecified"))
      (node (ref "R19") (pin "1") (pinfunction "1_1") (pintype "unspecified"))
      (node (ref "U1") (pin "21") (pinfunction "I2C3_CLK_(PH7)_21") (pintype "unspecified"))
    )
    (net (code "44") (name "I2C3_DAT") (class "Default")
      (node (ref "MB1") (pin "11") (pinfunction "I2C_SDA_11") (pintype "unspecified"))
      (node (ref "R20") (pin "1") (pinfunction "1_1") (pintype "unspecified"))
      (node (ref "U1") (pin "25") (pinfunction "I2C3_DAT_(PH8)_25") (pintype "unspecified"))
    )
    (net (code "45") (name "IO1_2") (class "Default")
      (node (ref "P3") (pin "2") (pinfunction "2_2") (pintype "unspecified"))
      (node (ref "U11") (pin "18") (pinfunction "GP6_18") (pintype "unspecified"))
    )
    (net (code "46") (name "IO1_3") (class "Default")
      (node (ref "P3") (pin "3") (pinfunction "3_3") (pintype "unspecified"))
      (node (ref "U11") (pin "17") (pinfunction "GP5_17") (pintype "unspecified"))
    )
    (net (code "47") (name "IO1_A1") (class "Default")
      (node (ref "P3") (pin "1") (pinfunction "1_1") (pintype "unspecified"))
      (node (ref "U1") (pin "88") (pinfunction "A04_(PB1)_88") (pintype "unspecified"))
    )
    (net (code "48") (name "LED_BLUE") (class "Default")
      (node (ref "R15") (pin "1") (pinfunction "1_1") (pintype "unspecified"))
      (node (ref "U1") (pin "32") (pinfunction "D11_(PC9)_32") (pintype "unspecified"))
    )
    (net (code "49") (name "LED_GREEN") (class "Default")
      (node (ref "R16") (pin "1") (pinfunction "1_1") (pintype "unspecified"))
      (node (ref "U1") (pin "30") (pinfunction "D10_(PC7)_30") (pintype "unspecified"))
    )
    (net (code "50") (name "LED_RED") (class "Default")
      (node (ref "R17") (pin "1") (pinfunction "1_1") (pintype "unspecified"))
      (node (ref "U1") (pin "29") (pinfunction "D09_(PC6)_29") (pintype "unspecified"))
    )
    (net (code "51") (name "MBUS1_CS") (class "Default")
      (node (ref "MB1") (pin "3") (pinfunction "CS_3") (pintype "unspecified"))
      (node (ref "U1") (pin "19") (pinfunction "D14_(PB12)_19") (pintype "unspecified"))
    )
    (net (code "52") (name "MBUS1_INT") (class "Default")
      (node (ref "MB1") (pin "15") (pinfunction "INT_15") (pintype "unspecified"))
      (node (ref "R7") (pin "2") (pinfunction "2_2") (pintype "unspecified"))
      (node (ref "U1") (pin "82") (pinfunction "OTG_FS_OC_(PC2)_82") (pintype "unspecified"))
    )
    (net (code "53") (name "MBUS1_RST") (class "Default")
      (node (ref "MB1") (pin "2") (pinfunction "RST_2") (pintype "unspecified"))
      (node (ref "U1") (pin "26") (pinfunction "D02_(PH10)_26") (pintype "unspecified"))
    )
    (net (code "54") (name "MBUS2_CS") (class "Default")
      (node (ref "MB2") (pin "3") (pinfunction "CS_3") (pintype "unspecified"))
      (node (ref "U11") (pin "14") (pinfunction "GP2_14") (pintype "unspecified"))
    )
    (net (code "55") (name "MBUS2_INT") (class "Default")
      (node (ref "MB2") (pin "15") (pinfunction "INT_15") (pintype "unspecified"))
      (node (ref "R9") (pin "2") (pinfunction "2_2") (pintype "unspecified"))
      (node (ref "U11") (pin "15") (pinfunction "GP3_15") (pintype "unspecified"))
    )
    (net (code "56") (name "MBUS2_RST") (class "Default")
      (node (ref "MB2") (pin "2") (pinfunction "RST_2") (pintype "unspecified"))
      (node (ref "U11") (pin "13") (pinfunction "GP1_13") (pintype "unspecified"))
    )
    (net (code "57") (name "MCP1_INT") (class "Default")
      (node (ref "U1") (pin "72") (pinfunction "A05_(PC0)_72") (pintype "unspecified"))
      (node (ref "U9") (pin "8") (pinfunction "INT_8") (pintype "unspecified"))
    )
    (net (code "58") (name "MCP2_INT") (class "Default")
      (node (ref "U1") (pin "31") (pinfunction "D19_(PC8)_31") (pintype "unspecified"))
      (node (ref "U11") (pin "8") (pinfunction "INT_8") (pintype "unspecified"))
    )
    (net (code "59") (name "MCP_RST") (class "Default")
      (node (ref "U1") (pin "53") (pinfunction "D05_(PB4)_53") (pintype "unspecified"))
      (node (ref "U11") (pin "6") (pinfunction "RESET#_6") (pintype "unspecified"))
      (node (ref "U12") (pin "6") (pinfunction "RESET#_6") (pintype "unspecified"))
      (node (ref "U9") (pin "6") (pinfunction "RESET#_6") (pintype "unspecified"))
    )
    (net (code "60") (name "Net-(D10-A)") (class "Default")
      (node (ref "D10") (pin "1") (pinfunction "A_1") (pintype "bidirectional"))
      (node (ref "Q2") (pin "3") (pinfunction "D_3") (pintype "unspecified"))
      (node (ref "U7") (pin "2") (pinfunction "2_2") (pintype "unspecified"))
    )
    (net (code "61") (name "Net-(Q1-D)") (class "Default")
      (node (ref "Q1") (pin "3") (pinfunction "D_3") (pintype "unspecified"))
      (node (ref "U14") (pin "1") (pinfunction "VCC_1") (pintype "unspecified"))
      (node (ref "U14") (pin "8") (pinfunction "LED_8") (pintype "unspecified"))
    )
    (net (code "62") (name "Net-(R12-Pad1)") (class "Default")
      (node (ref "R12") (pin "1") (pinfunction "1_1") (pintype "unspecified"))
      (node (ref "U7") (pin "1") (pinfunction "1_1") (pintype "unspecified"))
    )
    (net (code "63") (name "Net-(U2-CSB)") (class "Default")
      (node (ref "R4") (pin "2") (pinfunction "2_2") (pintype "unspecified"))
      (node (ref "U2") (pin "12") (pinfunction "CSB_12") (pintype "unspecified"))
    )
    (net (code "64") (name "Net-(U2-SDO)") (class "Default")
      (node (ref "R3") (pin "2") (pinfunction "2_2") (pintype "unspecified"))
      (node (ref "U2") (pin "1") (pinfunction "SDO_1") (pintype "unspecified"))
    )
    (net (code "65") (name "Net-(U4-CSB)") (class "Default")
      (node (ref "R6") (pin "1") (pinfunction "1_1") (pintype "unspecified"))
      (node (ref "U4") (pin "2") (pinfunction "CSB_2") (pintype "unspecified"))
    )
    (net (code "66") (name "Net-(U4-SDO)") (class "Default")
      (node (ref "R8") (pin "2") (pinfunction "2_2") (pintype "unspecified"))
      (node (ref "U4") (pin "5") (pinfunction "SDO_5") (pintype "unspecified"))
    )
    (net (code "67") (name "Net-(U6-ADDR)") (class "Default")
      (node (ref "R14") (pin "2") (pinfunction "2_2") (pintype "unspecified"))
      (node (ref "U6") (pin "2") (pinfunction "ADDR_2") (pintype "unspecified"))
    )
    (net (code "68") (name "Net-(U6-DVI)") (class "Default")
      (node (ref "C11") (pin "2") (pinfunction "2_2") (pintype "unspecified"))
      (node (ref "R13") (pin "1") (pinfunction "1_1") (pintype "unspecified"))
      (node (ref "U6") (pin "5") (pinfunction "DVI_5") (pintype "unspecified"))
    )
    (net (code "69") (name "Net-(U10-C1)") (class "Default")
      (node (ref "R17") (pin "2") (pinfunction "2_2") (pintype "unspecified"))
      (node (ref "U10") (pin "1") (pinfunction "C1_1") (pintype "unspecified"))
    )
    (net (code "70") (name "Net-(U10-C2)") (class "Default")
      (node (ref "R16") (pin "2") (pinfunction "2_2") (pintype "unspecified"))
      (node (ref "U10") (pin "2") (pinfunction "C2_2") (pintype "unspecified"))
    )
    (net (code "71") (name "Net-(U10-C3)") (class "Default")
      (node (ref "R15") (pin "2") (pinfunction "2_2") (pintype "unspecified"))
      (node (ref "U10") (pin "3") (pinfunction "C3_3") (pintype "unspecified"))
    )
    (net (code "72") (name "Net-(U15-COM1_RX)") (class "Default")
      (node (ref "R10") (pin "2") (pinfunction "2_2") (pintype "unspecified"))
      (node (ref "U15") (pin "14") (pinfunction "COM1_RX_14") (pintype "unspecified"))
    )
    (net (code "73") (name "Net-(U15-COM1_TX)") (class "Default")
      (node (ref "R18") (pin "2") (pinfunction "2_2") (pintype "unspecified"))
      (node (ref "U15") (pin "15") (pinfunction "COM1_TX_15") (pintype "unspecified"))
    )
    (net (code "74") (name "Net-(U17-Y)") (class "Default")
      (node (ref "U17") (pin "4") (pinfunction "Y_4") (pintype "unspecified"))
      (node (ref "U3") (pin "2") (pinfunction "RE#_2") (pintype "unspecified"))
      (node (ref "U3") (pin "3") (pinfunction "DE_3") (pintype "unspecified"))
    )
    (net (code "75") (name "RS485_A") (class "Default")
      (node (ref "P1") (pin "1") (pinfunction "1_1") (pintype "unspecified"))
      (node (ref "U3") (pin "6") (pinfunction "A_6") (pintype "unspecified"))
    )
    (net (code "76") (name "RS485_B") (class "Default")
      (node (ref "P1") (pin "2") (pinfunction "2_2") (pintype "unspecified"))
      (node (ref "U3") (pin "7") (pinfunction "B_7") (pintype "unspecified"))
    )
    (net (code "77") (name "SPI5_CIPO") (class "Default")
      (node (ref "MB1") (pin "5") (pinfunction "SPI_CIPO_5") (pintype "unspecified"))
      (node (ref "U1") (pin "71") (pinfunction "SPI5_CIPO_(PF8)_71") (pintype "unspecified"))
    )
    (net (code "78") (name "SPI5_CLK") (class "Default")
      (node (ref "MB1") (pin "4") (pinfunction "SPI_SCK_4") (pintype "unspecified"))
      (node (ref "U1") (pin "24") (pinfunction "SPI5_CLK_(PH6)_24") (pintype "unspecified"))
    )
    (net (code "79") (name "SPI5_COPI") (class "Default")
      (node (ref "MB1") (pin "6") (pinfunction "SPI_COPI_6") (pintype "unspecified"))
      (node (ref "U1") (pin "70") (pinfunction "SPI5_COPI_(PF9)_70") (pintype "unspecified"))
    )
    (net (code "80") (name "SPI_CIPO") (class "Default")
      (node (ref "MB2") (pin "5") (pinfunction "SPI_CIPO_5") (pintype "unspecified"))
      (node (ref "U1") (pin "38") (pinfunction "SPI3_CIPO_(PC11)_38") (pintype "unspecified"))
    )
    (net (code "81") (name "SPI_CLK") (class "Default")
      (node (ref "MB2") (pin "4") (pinfunction "SPI_SCK_4") (pintype "unspecified"))
      (node (ref "U1") (pin "37") (pinfunction "SPI3_CLK_(PC10)_37") (pintype "unspecified"))
      (node (ref "U14") (pin "7") (pinfunction "SCK_7") (pintype "unspecified"))
    )
    (net (code "82") (name "SPI_COPI") (class "Default")
      (node (ref "MB2") (pin "6") (pinfunction "SPI_COPI_6") (pintype "unspecified"))
      (node (ref "U1") (pin "61") (pinfunction "SPI3_COPI_(PB5)_61") (pintype "unspecified"))
      (node (ref "U14") (pin "6") (pinfunction "MOSI_6") (pintype "unspecified"))
    )
    (net (code "83") (name "UART1_A_RX") (class "Default")
      (node (ref "MB2") (pin "14") (pinfunction "UART_RX_14") (pintype "unspecified"))
      (node (ref "U16") (pin "1") (pinfunction "RXA_1") (pintype "unspecified"))
    )
    (net (code "84") (name "UART1_A_TX") (class "Default")
      (node (ref "MB2") (pin "13") (pinfunction "UART_TX_13") (pintype "unspecified"))
      (node (ref "U16") (pin "32") (pinfunction "TXA_32") (pintype "unspecified"))
    )
    (net (code "85") (name "UART1_B_RTS") (class "Default")
      (node (ref "U16") (pin "16") (pinfunction "RTSB#_16") (pintype "unspecified"))
      (node (ref "U17") (pin "2") (pinfunction "A_2") (pintype "unspecified"))
    )
    (net (code "86") (name "UART1_B_RX") (class "Default")
      (node (ref "U16") (pin "23") (pinfunction "RXB_23") (pintype "unspecified"))
      (node (ref "U3") (pin "1") (pinfunction "RO_1") (pintype "unspecified"))
    )
    (net (code "87") (name "UART1_B_TX") (class "Default")
      (node (ref "U16") (pin "22") (pinfunction "TXB_22") (pintype "unspecified"))
      (node (ref "U3") (pin "4") (pinfunction "DI_4") (pintype "unspecified"))
    )
    (net (code "88") (name "UART1_INT") (class "Default")
      (node (ref "R22") (pin "2") (pinfunction "2_2") (pintype "unspecified"))
      (node (ref "U16") (pin "14") (pinfunction "IRQ#_14") (pintype "unspecified"))
    )
    (net (code "89") (name "UART1_OSCI") (class "Default")
      (node (ref "OSC1") (pin "3") (pinfunction "OUTPUT_3") (pintype "unspecified"))
      (node (ref "U16") (pin "3") (pinfunction "XTAL1_3") (pintype "unspecified"))
    )
    (net (code "90") (name "UART1_RST") (class "Default")
      (node (ref "R21") (pin "2") (pinfunction "2_2") (pintype "unspecified"))
      (node (ref "U16") (pin "2") (pinfunction "RESET#_2") (pintype "unspecified"))
    )
    (net (code "91") (name "USB_D_N") (class "Default")
      (node (ref "U1") (pin "40") (pinfunction "USB_D_N_40") (pintype "unspecified"))
      (node (ref "U13") (pin "20") (pinfunction "USB_D_N_20") (pintype "unspecified"))
    )
    (net (code "92") (name "USB_D_P") (class "Default")
      (node (ref "U1") (pin "41") (pinfunction "USB_D_P_41") (pintype "unspecified"))
      (node (ref "U13") (pin "19") (pinfunction "USB_D_P_19") (pintype "unspecified"))
    )
    (net (code "93") (name "VBUS") (class "Default")
      (node (ref "U1") (pin "35") (pinfunction "OTG_VBUS_(PA9)_35") (pintype "unspecified"))
      (node (ref "U13") (pin "15") (pinfunction "VBUS_15") (pintype "unspecified"))
    )
    (net (code "94") (name "unconnected-(CN1-Pad5)") (class "Default")
      (node (ref "CN1") (pin "5") (pinfunction "5_5") (pintype "unspecified+no_connect"))
    )
    (net (code "95") (name "unconnected-(CN1-Pad6)") (class "Default")
      (node (ref "CN1") (pin "6") (pinfunction "6_6") (pintype "unspecified+no_connect"))
    )
    (net (code "96") (name "unconnected-(J1-PadSS1)") (class "Default")
      (node (ref "J1") (pin "SS1") (pinfunction "SS1_SS1") (pintype "unspecified+no_connect"))
    )
    (net (code "97") (name "unconnected-(J1-PadSS2)") (class "Default")
      (node (ref "J1") (pin "SS2") (pinfunction "SS2_SS2") (pintype "unspecified+no_connect"))
    )
    (net (code "98") (name "unconnected-(J2-PadSS1)") (class "Default")
      (node (ref "J2") (pin "SS1") (pinfunction "SS1_SS1") (pintype "unspecified+no_connect"))
    )
    (net (code "99") (name "unconnected-(J2-PadSS2)") (class "Default")
      (node (ref "J2") (pin "SS2") (pinfunction "SS2_SS2") (pintype "unspecified+no_connect"))
    )
    (net (code "100") (name "unconnected-(J3-PadSS1)") (class "Default")
      (node (ref "J3") (pin "SS1") (pinfunction "SS1_SS1") (pintype "unspecified+no_connect"))
    )
    (net (code "101") (name "unconnected-(J3-PadSS2)") (class "Default")
      (node (ref "J3") (pin "SS2") (pinfunction "SS2_SS2") (pintype "unspecified+no_connect"))
    )
    (net (code "102") (name "unconnected-(OSC1-Tri-State(STBY)-Pad1)") (class "Default")
      (node (ref "OSC1") (pin "1") (pinfunction "Tri-State(STBY)_1") (pintype "unspecified+no_connect"))
    )
    (net (code "103") (name "unconnected-(S5-1-Pad3)") (class "Default")
      (node (ref "S5") (pin "3") (pinfunction "1_3") (pintype "unspecified+no_connect"))
    )
    (net (code "104") (name "unconnected-(S5-1-Pad4)") (class "Default")
      (node (ref "S5") (pin "4") (pinfunction "1_4") (pintype "unspecified+no_connect"))
    )
    (net (code "105") (name "unconnected-(S5-1-Pad6)") (class "Default")
      (node (ref "S5") (pin "6") (pinfunction "1_6") (pintype "unspecified+no_connect"))
    )
    (net (code "106") (name "unconnected-(S5-2-Pad5)") (class "Default")
      (node (ref "S5") (pin "5") (pinfunction "2_5") (pintype "unspecified+no_connect"))
    )
    (net (code "107") (name "unconnected-(U1-D06_(PB13)-Pad20)") (class "Default")
      (node (ref "U1") (pin "20") (pinfunction "D06_(PB13)_20") (pintype "unspecified+no_connect"))
    )
    (net (code "108") (name "unconnected-(U1-D15{slash}SD2_D3_(PG12)-Pad56)") (class "Default")
      (node (ref "U1") (pin "56") (pinfunction "D15/SD2_D3_(PG12)_56") (pintype "unspecified+no_connect"))
    )
    (net (code "109") (name "unconnected-(U1-D18_(PA10)-Pad36)") (class "Default")
      (node (ref "U1") (pin "36") (pinfunction "D18_(PA10)_36") (pintype "unspecified+no_connect"))
    )
    (net (code "110") (name "unconnected-(U1-ETH_CRS_DV_(PA7)-Pad87)") (class "Default")
      (node (ref "U1") (pin "87") (pinfunction "ETH_CRS_DV_(PA7)_87") (pintype "unspecified+no_connect"))
    )
    (net (code "111") (name "unconnected-(U1-ETH_IRQ_(PH14)-Pad33)") (class "Default")
      (node (ref "U1") (pin "33") (pinfunction "ETH_IRQ_(PH14)_33") (pintype "unspecified+no_connect"))
    )
    (net (code "112") (name "unconnected-(U1-ETH_MDC_(PC1)-Pad73)") (class "Default")
      (node (ref "U1") (pin "73") (pinfunction "ETH_MDC_(PC1)_73") (pintype "unspecified+no_connect"))
    )
    (net (code "113") (name "unconnected-(U1-ETH_MDIO_(PA2)-Pad77)") (class "Default")
      (node (ref "U1") (pin "77") (pinfunction "ETH_MDIO_(PA2)_77") (pintype "unspecified+no_connect"))
    )
    (net (code "114") (name "unconnected-(U1-ETH_REF_CLK_(PA1)-Pad75)") (class "Default")
      (node (ref "U1") (pin "75") (pinfunction "ETH_REF_CLK_(PA1)_75") (pintype "unspecified+no_connect"))
    )
    (net (code "115") (name "unconnected-(U1-ETH_RXD0_(PC4)-Pad84)") (class "Default")
      (node (ref "U1") (pin "84") (pinfunction "ETH_RXD0_(PC4)_84") (pintype "unspecified+no_connect"))
    )
    (net (code "116") (name "unconnected-(U1-ETH_RXD1_(PC5)-Pad85)") (class "Default")
      (node (ref "U1") (pin "85") (pinfunction "ETH_RXD1_(PC5)_85") (pintype "unspecified+no_connect"))
    )
    (net (code "117") (name "unconnected-(U1-ETH_TXD0_(PG13)-Pad55)") (class "Default")
      (node (ref "U1") (pin "55") (pinfunction "ETH_TXD0_(PG13)_55") (pintype "unspecified+no_connect"))
    )
    (net (code "118") (name "unconnected-(U1-ETH_TXD1_(PG14)-Pad60)") (class "Default")
      (node (ref "U1") (pin "60") (pinfunction "ETH_TXD1_(PG14)_60") (pintype "unspecified+no_connect"))
    )
    (net (code "119") (name "unconnected-(U1-ETH_TX_EN_(PB11)-Pad16)") (class "Default")
      (node (ref "U1") (pin "16") (pinfunction "ETH_TX_EN_(PB11)_16") (pintype "unspecified+no_connect"))
    )
    (net (code "120") (name "unconnected-(U1-OTG_PWRON_(PH12)-Pad27)") (class "Default")
      (node (ref "U1") (pin "27") (pinfunction "OTG_PWRON_(PH12)_27") (pintype "unspecified+no_connect"))
    )
    (net (code "121") (name "unconnected-(U1-SD2_CLK_(PD6)-Pad47)") (class "Default")
      (node (ref "U1") (pin "47") (pinfunction "SD2_CLK_(PD6)_47") (pintype "unspecified+no_connect"))
    )
    (net (code "122") (name "unconnected-(U1-SD2_CMD_(PD7)-Pad48)") (class "Default")
      (node (ref "U1") (pin "48") (pinfunction "SD2_CMD_(PD7)_48") (pintype "unspecified+no_connect"))
    )
    (net (code "123") (name "unconnected-(U1-SD2_D0_(PG9)-Pad52)") (class "Default")
      (node (ref "U1") (pin "52") (pinfunction "SD2_D0_(PG9)_52") (pintype "unspecified+no_connect"))
    )
    (net (code "124") (name "unconnected-(U1-SD2_D1_(PG10)-Pad51)") (class "Default")
      (node (ref "U1") (pin "51") (pinfunction "SD2_D1_(PG10)_51") (pintype "unspecified+no_connect"))
    )
    (net (code "125") (name "unconnected-(U1-SD2_D2_(PG11)-Pad54)") (class "Default")
      (node (ref "U1") (pin "54") (pinfunction "SD2_D2_(PG11)_54") (pintype "unspecified+no_connect"))
    )
    (net (code "126") (name "unconnected-(U1-SD2_IN_L_(PG6)-Pad28)") (class "Default")
      (node (ref "U1") (pin "28") (pinfunction "SD2_IN_L_(PG6)_28") (pintype "unspecified+no_connect"))
    )
    (net (code "127") (name "unconnected-(U2-ASCX-Pad3)") (class "Default")
      (node (ref "U2") (pin "3") (pinfunction "ASCX_3") (pintype "unspecified+no_connect"))
    )
    (net (code "128") (name "unconnected-(U2-ASDX-Pad2)") (class "Default")
      (node (ref "U2") (pin "2") (pinfunction "ASDX_2") (pintype "unspecified+no_connect"))
    )
    (net (code "129") (name "unconnected-(U2-INT2-Pad9)") (class "Default")
      (node (ref "U2") (pin "9") (pinfunction "INT2_9") (pintype "unspecified+no_connect"))
    )
    (net (code "130") (name "unconnected-(U2-OCSB-Pad10)") (class "Default")
      (node (ref "U2") (pin "10") (pinfunction "OCSB_10") (pintype "unspecified+no_connect"))
    )
    (net (code "131") (name "unconnected-(U2-OSDO-Pad11)") (class "Default")
      (node (ref "U2") (pin "11") (pinfunction "OSDO_11") (pintype "unspecified+no_connect"))
    )
    (net (code "132") (name "unconnected-(U6-EP-Pad7)") (class "Default")
      (node (ref "U6") (pin "7") (pinfunction "EP_7") (pintype "unspecified+no_connect"))
    )
    (net (code "133") (name "unconnected-(U9-NC-Pad7)") (class "Default")
      (node (ref "U9") (pin "7") (pinfunction "NC_7") (pintype "unspecified+no_connect"))
    )
    (net (code "134") (name "unconnected-(U9-N{slash}C-Pad10)") (class "Default")
      (node (ref "U9") (pin "10") (pinfunction "N/C_10") (pintype "unspecified+no_connect"))
    )
    (net (code "135") (name "unconnected-(U9-N{slash}C-Pad11)") (class "Default")
      (node (ref "U9") (pin "11") (pinfunction "N/C_11") (pintype "unspecified+no_connect"))
    )
    (net (code "136") (name "unconnected-(U11-GP0-Pad12)") (class "Default")
      (node (ref "U11") (pin "12") (pinfunction "GP0_12") (pintype "unspecified+no_connect"))
    )
    (net (code "137") (name "unconnected-(U11-GP4-Pad16)") (class "Default")
      (node (ref "U11") (pin "16") (pinfunction "GP4_16") (pintype "unspecified+no_connect"))
    )
    (net (code "138") (name "unconnected-(U11-NC-Pad7)") (class "Default")
      (node (ref "U11") (pin "7") (pinfunction "NC_7") (pintype "unspecified+no_connect"))
    )
    (net (code "139") (name "unconnected-(U11-N{slash}C-Pad10)") (class "Default")
      (node (ref "U11") (pin "10") (pinfunction "N/C_10") (pintype "unspecified+no_connect"))
    )
    (net (code "140") (name "unconnected-(U11-N{slash}C-Pad11)") (class "Default")
      (node (ref "U11") (pin "11") (pinfunction "N/C_11") (pintype "unspecified+no_connect"))
    )
    (net (code "141") (name "unconnected-(U12-INT-Pad8)") (class "Default")
      (node (ref "U12") (pin "8") (pinfunction "INT_8") (pintype "unspecified+no_connect"))
    )
    (net (code "142") (name "unconnected-(U12-NC-Pad7)") (class "Default")
      (node (ref "U12") (pin "7") (pinfunction "NC_7") (pintype "unspecified+no_connect"))
    )
    (net (code "143") (name "unconnected-(U12-N{slash}C-Pad10)") (class "Default")
      (node (ref "U12") (pin "10") (pinfunction "N/C_10") (pintype "unspecified+no_connect"))
    )
    (net (code "144") (name "unconnected-(U12-N{slash}C-Pad11)") (class "Default")
      (node (ref "U12") (pin "11") (pinfunction "N/C_11") (pintype "unspecified+no_connect"))
    )
    (net (code "145") (name "unconnected-(U14-MISO-Pad9)") (class "Default")
      (node (ref "U14") (pin "9") (pinfunction "MISO_9") (pintype "unspecified+no_connect"))
    )
    (net (code "146") (name "unconnected-(U14-SD_CS-Pad15)") (class "Default")
      (node (ref "U14") (pin "15") (pinfunction "SD_CS_15") (pintype "unspecified+no_connect"))
    )
    (net (code "147") (name "unconnected-(U14-SD_MISO-Pad17)") (class "Default")
      (node (ref "U14") (pin "17") (pinfunction "SD_MISO_17") (pintype "unspecified+no_connect"))
    )
    (net (code "148") (name "unconnected-(U14-SD_MOSI-Pad16)") (class "Default")
      (node (ref "U14") (pin "16") (pinfunction "SD_MOSI_16") (pintype "unspecified+no_connect"))
    )
    (net (code "149") (name "unconnected-(U14-SD_SCK-Pad18)") (class "Default")
      (node (ref "U14") (pin "18") (pinfunction "SD_SCK_18") (pintype "unspecified+no_connect"))
    )
    (net (code "150") (name "unconnected-(U14-T_CLK-Pad10)") (class "Default")
      (node (ref "U14") (pin "10") (pinfunction "T_CLK_10") (pintype "unspecified+no_connect"))
    )
    (net (code "151") (name "unconnected-(U14-T_CS-Pad11)") (class "Default")
      (node (ref "U14") (pin "11") (pinfunction "T_CS_11") (pintype "unspecified+no_connect"))
    )
    (net (code "152") (name "unconnected-(U14-T_DIN-Pad12)") (class "Default")
      (node (ref "U14") (pin "12") (pinfunction "T_DIN_12") (pintype "unspecified+no_connect"))
    )
    (net (code "153") (name "unconnected-(U14-T_DO-Pad13)") (class "Default")
      (node (ref "U14") (pin "13") (pinfunction "T_DO_13") (pintype "unspecified+no_connect"))
    )
    (net (code "154") (name "unconnected-(U14-T_IRQ-Pad14)") (class "Default")
      (node (ref "U14") (pin "14") (pinfunction "T_IRQ_14") (pintype "unspecified+no_connect"))
    )
    (net (code "155") (name "unconnected-(U16-CTSA#-Pad31)") (class "Default")
      (node (ref "U16") (pin "31") (pinfunction "CTSA#_31") (pintype "unspecified+no_connect"))
    )
    (net (code "156") (name "unconnected-(U16-CTSB#-Pad15)") (class "Default")
      (node (ref "U16") (pin "15") (pinfunction "CTSB#_15") (pintype "unspecified+no_connect"))
    )
    (net (code "157") (name "unconnected-(U16-GPIO0{slash}DSRB#-Pad17)") (class "Default")
      (node (ref "U16") (pin "17") (pinfunction "GPIO0/DSRB#_17") (pintype "unspecified+no_connect"))
    )
    (net (code "158") (name "unconnected-(U16-GPIO1{slash}DTRB#-Pad18)") (class "Default")
      (node (ref "U16") (pin "18") (pinfunction "GPIO1/DTRB#_18") (pintype "unspecified+no_connect"))
    )
    (net (code "159") (name "unconnected-(U16-GPIO2{slash}CDB#-Pad19)") (class "Default")
      (node (ref "U16") (pin "19") (pinfunction "GPIO2/CDB#_19") (pintype "unspecified+no_connect"))
    )
    (net (code "160") (name "unconnected-(U16-GPIO3{slash}RIB#-Pad20)") (class "Default")
      (node (ref "U16") (pin "20") (pinfunction "GPIO3/RIB#_20") (pintype "unspecified+no_connect"))
    )
    (net (code "161") (name "unconnected-(U16-GPIO4{slash}DSRA#-Pad24)") (class "Default")
      (node (ref "U16") (pin "24") (pinfunction "GPIO4/DSRA#_24") (pintype "unspecified+no_connect"))
    )
    (net (code "162") (name "unconnected-(U16-GPIO5{slash}DTRA#-Pad25)") (class "Default")
      (node (ref "U16") (pin "25") (pinfunction "GPIO5/DTRA#_25") (pintype "unspecified+no_connect"))
    )
    (net (code "163") (name "unconnected-(U16-GPIO6{slash}CDA#-Pad26)") (class "Default")
      (node (ref "U16") (pin "26") (pinfunction "GPIO6/CDA#_26") (pintype "unspecified+no_connect"))
    )
    (net (code "164") (name "unconnected-(U16-GPIO7{slash}RIA#-Pad27)") (class "Default")
      (node (ref "U16") (pin "27") (pinfunction "GPIO7/RIA#_27") (pintype "unspecified+no_connect"))
    )
    (net (code "165") (name "unconnected-(U16-RTSA#-Pad30)") (class "Default")
      (node (ref "U16") (pin "30") (pinfunction "RTSA#_30") (pintype "unspecified+no_connect"))
    )
    (net (code "166") (name "unconnected-(U16-SO-Pad9)") (class "Default")
      (node (ref "U16") (pin "9") (pinfunction "SO_9") (pintype "unspecified+no_connect"))
    )
    (net (code "167") (name "unconnected-(U16-XTAL2-Pad4)") (class "Default")
      (node (ref "U16") (pin "4") (pinfunction "XTAL2_4") (pintype "unspecified+no_connect"))
    )
    (net (code "168") (name "unconnected-(U17-NC-Pad1)") (class "Default")
      (node (ref "U17") (pin "1") (pinfunction "NC_1") (pintype "unspecified+no_connect"))
    )
    (net (code "169") (name "unconnected-(U17-NC-Pad5)") (class "Default")
      (node (ref "U17") (pin "5") (pinfunction "NC_5") (pintype "unspecified+no_connect"))
    )
  )
)
